# adc08200.net
KiCad netlist of a schematic drawn in Altium Designer
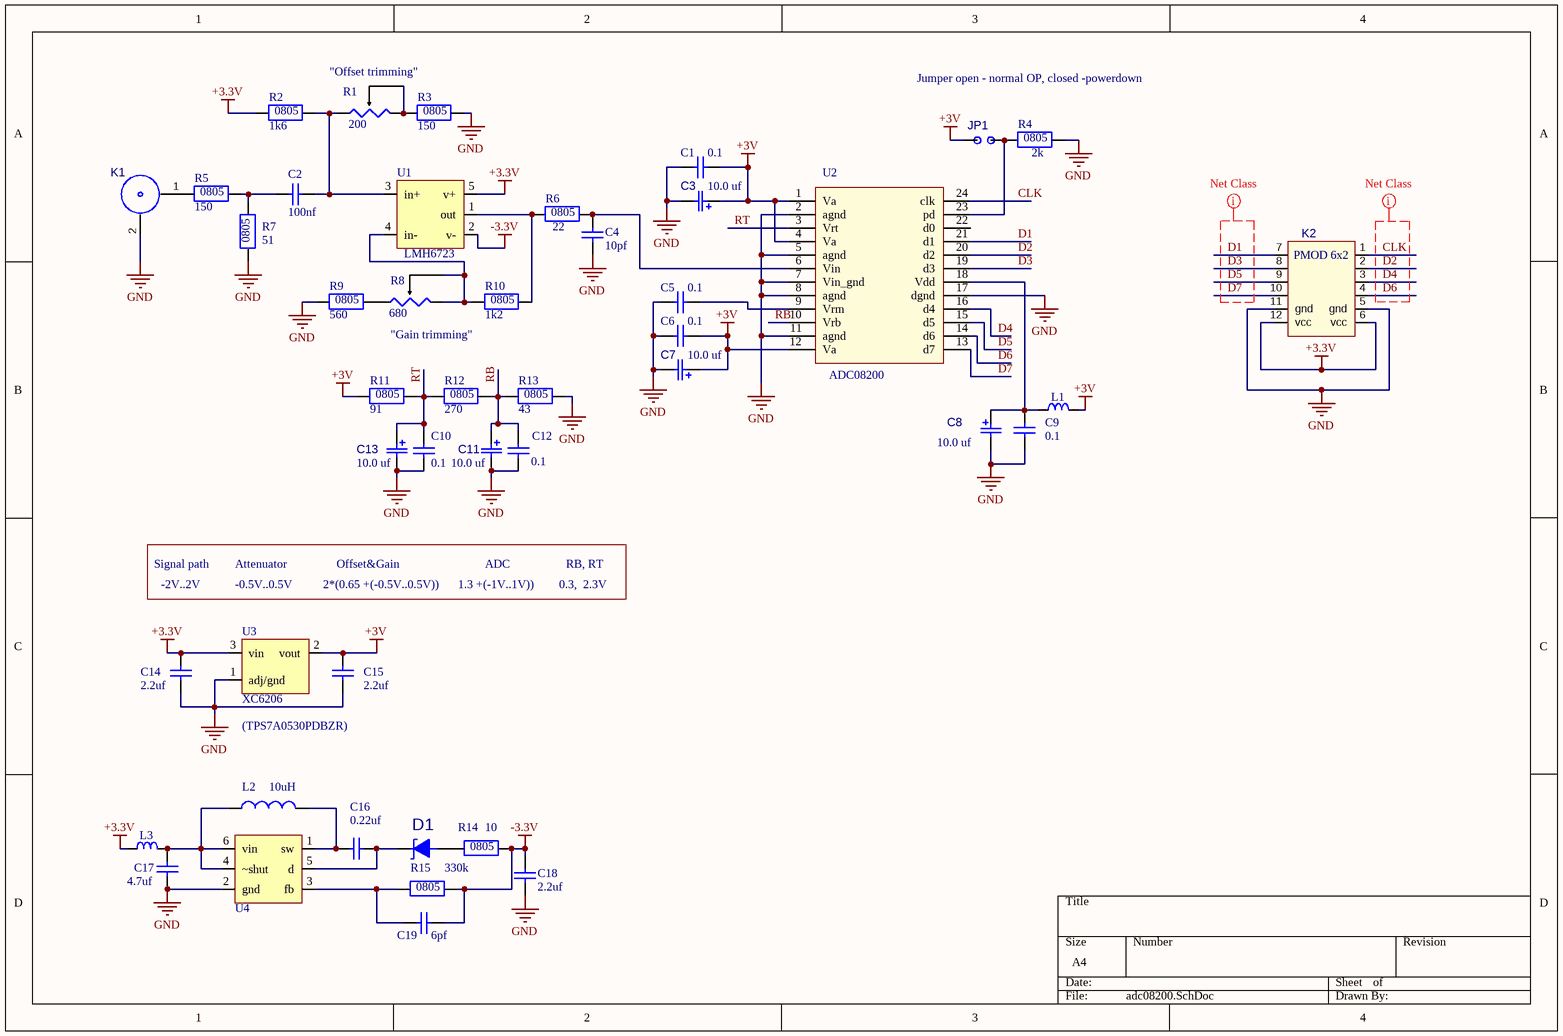
[diagram p0: adc08200.SchDoc]

(export (version "E")
  (design (tool "Eeschema 10.0.6"))
  (components
    (comp (ref "C1")
      (value "0.1")
      (footprint "SM0805")
      (description "Capacitor")
      (fields (field (name "Comment") "cap0805") (field (name "PUBLISHER") "Altium Limited"))
      (libsource (lib "alt2017") (part "cap0805"))
    )
    (comp (ref "C2")
      (value "100nf")
      (footprint "SM0805")
      (description "Capacitor")
      (fields (field (name "Comment") "cap0805") (field (name "PUBLISHER") "Altium Limited"))
      (libsource (lib "alt2017") (part "cap0805"))
    )
    (comp (ref "C3")
      (value "CAP_POL_SMA")
      (footprint "CAP_POL_SMA (3216)")
      (description "CAP_POL_SMA(3216)")
      (fields (field (name "ALTIUM_UNNAMED_1") "10.0 uf"))
      (libsource (lib "alt2017") (part "CAP_POL_SMA"))
    )
    (comp (ref "C4")
      (value "10pf")
      (footprint "SM0805")
      (description "Capacitor")
      (fields (field (name "Comment") "cap0805") (field (name "PUBLISHER") "Altium Limited"))
      (libsource (lib "alt2017") (part "cap0805"))
    )
    (comp (ref "C5")
      (value "0.1")
      (footprint "SM0805")
      (description "Capacitor")
      (fields (field (name "Comment") "cap0805") (field (name "PUBLISHER") "Altium Limited"))
      (libsource (lib "alt2017") (part "cap0805"))
    )
    (comp (ref "C6")
      (value "0.1")
      (footprint "SM0805")
      (description "Capacitor")
      (fields (field (name "Comment") "cap0805") (field (name "PUBLISHER") "Altium Limited"))
      (libsource (lib "alt2017") (part "cap0805"))
    )
    (comp (ref "C7")
      (value "CAP_POL_SMA")
      (footprint "CAP_POL_SMA (3216)")
      (description "CAP_POL_SMA(3216)")
      (fields (field (name "ALTIUM_UNNAMED_1") "10.0 uf"))
      (libsource (lib "alt2017") (part "CAP_POL_SMA"))
    )
    (comp (ref "C8")
      (value "CAP_POL_SMA")
      (footprint "CAP_POL_SMA (3216)")
      (description "CAP_POL_SMA(3216)")
      (fields (field (name "ALTIUM_UNNAMED_1") "10.0 uf"))
      (libsource (lib "alt2017") (part "CAP_POL_SMA"))
    )
    (comp (ref "C9")
      (value "0.1")
      (footprint "SM0805")
      (description "Capacitor")
      (fields (field (name "Comment") "cap0805") (field (name "PUBLISHER") "Altium Limited"))
      (libsource (lib "alt2017") (part "cap0805"))
    )
    (comp (ref "C10")
      (value "0.1")
      (footprint "SM0805")
      (description "Capacitor")
      (fields (field (name "Comment") "cap0805") (field (name "PUBLISHER") "Altium Limited"))
      (libsource (lib "alt2017") (part "cap0805"))
    )
    (comp (ref "C11")
      (value "CAP_POL_SMA")
      (footprint "CAP_POL_SMA (3216)")
      (description "CAP_POL_SMA(3216)")
      (fields (field (name "ALTIUM_UNNAMED_1") "10.0 uf"))
      (libsource (lib "alt2017") (part "CAP_POL_SMA"))
    )
    (comp (ref "C12")
      (value "0.1")
      (footprint "SM0805")
      (description "Capacitor")
      (fields (field (name "Comment") "cap0805") (field (name "PUBLISHER") "Altium Limited"))
      (libsource (lib "alt2017") (part "cap0805"))
    )
    (comp (ref "C13")
      (value "CAP_POL_SMA")
      (footprint "CAP_POL_SMA (3216)")
      (description "CAP_POL_SMA(3216)")
      (fields (field (name "ALTIUM_UNNAMED_1") "10.0 uf"))
      (libsource (lib "alt2017") (part "CAP_POL_SMA"))
    )
    (comp (ref "C14")
      (value "2.2uf")
      (footprint "SM0805")
      (description "Capacitor")
      (fields (field (name "Comment") "cap0805") (field (name "PUBLISHER") "Altium Limited"))
      (libsource (lib "alt2017") (part "cap0805"))
    )
    (comp (ref "C15")
      (value "2.2uf")
      (footprint "SM0805")
      (description "Capacitor")
      (fields (field (name "Comment") "cap0805") (field (name "PUBLISHER") "Altium Limited"))
      (libsource (lib "alt2017") (part "cap0805"))
    )
    (comp (ref "C16")
      (value "0.22uf")
      (footprint "SM0805")
      (description "Capacitor")
      (fields (field (name "Comment") "cap0805") (field (name "PUBLISHER") "Altium Limited"))
      (libsource (lib "alt2017") (part "cap0805"))
    )
    (comp (ref "C17")
      (value "4.7uf")
      (footprint "SM0805")
      (description "Capacitor")
      (fields (field (name "Comment") "cap0805") (field (name "PUBLISHER") "Altium Limited"))
      (libsource (lib "alt2017") (part "cap0805"))
    )
    (comp (ref "C18")
      (value "2.2uf")
      (footprint "SM0805")
      (description "Capacitor")
      (fields (field (name "Comment") "cap0805") (field (name "PUBLISHER") "Altium Limited"))
      (libsource (lib "alt2017") (part "cap0805"))
    )
    (comp (ref "C19")
      (value "6pf")
      (footprint "SM0805")
      (description "Capacitor")
      (fields (field (name "Comment") "cap0805") (field (name "PUBLISHER") "Altium Limited"))
      (libsource (lib "alt2017") (part "cap0805"))
    )
    (comp (ref "D1")
      (value "DiodeShottky_SOD323")
      (footprint "SOD323")
      (description "SOD323")
      (libsource (lib "alt2017") (part "DiodeShottky_SOD323"))
    )
    (comp (ref "JP1") (value "JUMPER2") (footprint "JUMPER2") (libsource (lib "alt2017") (part "JUMPER2")))
    (comp (ref "K1")
      (value "SMA_Edge")
      (footprint "AMPHENOL_132357-11")
      (libsource (lib "alt2017") (part "SMA_Edge"))
    )
    (comp (ref "K2")
      (value "PMOD_6x2_right_angle")
      (footprint "PMOD_6x2_right_ANGLE")
      (libsource (lib "alt2017") (part "PMOD_6x2_right_angle"))
    )
    (comp (ref "L1")
      (value "75R@100MHz")
      (footprint "SM_0805_INDUCTANCE _3D")
      (description "chip inductance")
      (fields
        (field (name "PART NUMBER") "IND0805_MURATA_BLM21BB750SN1D")
        (field (name "POWER") "700mA")
        (field (name "AUTHOR") "S. Jafar")
      )
      (libsource (lib "alt2017") (part "Ind_Chip_0805"))
    )
    (comp (ref "L2")
      (value "inductance SMT 3.2x4.5 mm")
      (footprint "inductor_LQH43PN")
      (fields (field (name "ALTIUM_UNNAMED_1") "10uH"))
      (libsource (lib "alt2017") (part "inductor_LQH43PN"))
    )
    (comp (ref "L3")
      (value "75R@100MHz")
      (footprint "SM_0805_INDUCTANCE _3D")
      (description "chip inductance")
      (fields
        (field (name "PART NUMBER") "IND0805_MURATA_BLM21BB750SN1D")
        (field (name "POWER") "700mA")
        (field (name "AUTHOR") "S. Jafar")
      )
      (libsource (lib "alt2017") (part "Ind_Chip_0805"))
    )
    (comp (ref "R1")
      (value "200")
      (footprint "TRIM_BOURNS_3223W")
      (description "Trimmer  Bourns  3223W")
      (fields (field (name "Comment") "res_var_SMT") (field (name "PUBLISHER") "Altium Limited"))
      (libsource (lib "alt2017") (part "res_var_SMT"))
    )
    (comp (ref "R2")
      (value "1k6")
      (footprint "SM0805")
      (description "Resistor")
      (fields (field (name "Comment") "res0805_EU") (field (name "PUBLISHER") "Altium Limited"))
      (libsource (lib "alt2017") (part "res0805_EU"))
    )
    (comp (ref "R3")
      (value "150")
      (footprint "SM0805")
      (description "Resistor")
      (fields (field (name "Comment") "res0805_EU") (field (name "PUBLISHER") "Altium Limited"))
      (libsource (lib "alt2017") (part "res0805_EU"))
    )
    (comp (ref "R4")
      (value "2k")
      (footprint "SM0805")
      (description "Resistor")
      (fields (field (name "Comment") "res0805_EU") (field (name "PUBLISHER") "Altium Limited"))
      (libsource (lib "alt2017") (part "res0805_EU"))
    )
    (comp (ref "R5")
      (value "150")
      (footprint "SM0805")
      (description "Resistor")
      (fields (field (name "Comment") "res0805_EU") (field (name "PUBLISHER") "Altium Limited"))
      (libsource (lib "alt2017") (part "res0805_EU"))
    )
    (comp (ref "R6")
      (value "22")
      (footprint "SM0805")
      (description "Resistor")
      (fields (field (name "Comment") "res0805_EU") (field (name "PUBLISHER") "Altium Limited"))
      (libsource (lib "alt2017") (part "res0805_EU"))
    )
    (comp (ref "R7")
      (value "51")
      (footprint "SM0805")
      (description "Resistor")
      (fields (field (name "Comment") "res0805_EU") (field (name "PUBLISHER") "Altium Limited"))
      (libsource (lib "") (part "res0805_EU_1"))
    )
    (comp (ref "R8")
      (value "680")
      (footprint "TRIM_BOURNS_3223W")
      (description "Trimmer  Bourns  3223W")
      (fields (field (name "Comment") "res_var_SMT") (field (name "PUBLISHER") "Altium Limited"))
      (libsource (lib "alt2017") (part "res_var_SMT"))
    )
    (comp (ref "R9")
      (value "560")
      (footprint "SM0805")
      (description "Resistor")
      (fields (field (name "Comment") "res0805_EU") (field (name "PUBLISHER") "Altium Limited"))
      (libsource (lib "alt2017") (part "res0805_EU"))
    )
    (comp (ref "R10")
      (value "1k2")
      (footprint "SM0805")
      (description "Resistor")
      (fields (field (name "Comment") "res0805_EU") (field (name "PUBLISHER") "Altium Limited"))
      (libsource (lib "alt2017") (part "res0805_EU"))
    )
    (comp (ref "R11")
      (value "91")
      (footprint "SM0805")
      (description "Resistor")
      (fields (field (name "Comment") "res0805_EU") (field (name "PUBLISHER") "Altium Limited"))
      (libsource (lib "alt2017") (part "res0805_EU"))
    )
    (comp (ref "R12")
      (value "270")
      (footprint "SM0805")
      (description "Resistor")
      (fields (field (name "Comment") "res0805_EU") (field (name "PUBLISHER") "Altium Limited"))
      (libsource (lib "alt2017") (part "res0805_EU"))
    )
    (comp (ref "R13")
      (value "43")
      (footprint "SM0805")
      (description "Resistor")
      (fields (field (name "Comment") "res0805_EU") (field (name "PUBLISHER") "Altium Limited"))
      (libsource (lib "alt2017") (part "res0805_EU"))
    )
    (comp (ref "R14")
      (value "10")
      (footprint "SM0805")
      (description "Resistor")
      (fields (field (name "Comment") "res0805_EU") (field (name "PUBLISHER") "Altium Limited"))
      (libsource (lib "alt2017") (part "res0805_EU"))
    )
    (comp (ref "R15")
      (value "330k")
      (footprint "SM0805")
      (description "Resistor")
      (fields (field (name "Comment") "res0805_EU") (field (name "PUBLISHER") "Altium Limited"))
      (libsource (lib "alt2017") (part "res0805_EU"))
    )
    (comp (ref "U1")
      (value "LMH6723")
      (footprint "SOT-23_5")
      (description "current feedback OPAMP")
      (libsource (lib "alt2017") (part "LMH6723"))
    )
    (comp (ref "U2")
      (value "ADC08200")
      (footprint "SSOP-24")
      (description "soic28 with thermalpad")
      (libsource (lib "alt2017") (part "ADC08200"))
    )
    (comp (ref "U3")
      (value "XC6206")
      (footprint "SOT-23")
      (description "SOT-23-3 ldo")
      (libsource (lib "alt2017") (part "XC6206"))
    )
    (comp (ref "U4")
      (value "LT3483")
      (footprint "SOT-23_6")
      (description "dc/dc tsot23-6")
      (libsource (lib "alt2017") (part "LT3483"))
    )
  )
  (nets
    (net (code "1") (name "+3.3V") (class "Default")
      (node (ref "C14") (pin "2") (pinfunction "2_2") (pintype "passive"))
      (node (ref "K2") (pin "12") (pinfunction "vcc_12") (pintype "passive"))
      (node (ref "K2") (pin "6") (pinfunction "vcc_6") (pintype "passive"))
      (node (ref "L3") (pin "1") (pinfunction "1_1") (pintype "passive"))
      (node (ref "R2") (pin "1") (pinfunction "1_1") (pintype "passive"))
      (node (ref "U1") (pin "5") (pinfunction "v+_5") (pintype "passive"))
      (node (ref "U3") (pin "3") (pinfunction "vin_3") (pintype "passive"))
    )
    (net (code "2") (name "+3V") (class "Default")
      (node (ref "C1") (pin "2") (pinfunction "2_2") (pintype "passive"))
      (node (ref "C15") (pin "2") (pinfunction "2_2") (pintype "passive"))
      (node (ref "C3") (pin "1") (pinfunction "a_1") (pintype "passive"))
      (node (ref "C6") (pin "2") (pinfunction "2_2") (pintype "passive"))
      (node (ref "C7") (pin "1") (pinfunction "a_1") (pintype "passive"))
      (node (ref "JP1") (pin "2") (pinfunction "2_2") (pintype "passive"))
      (node (ref "L1") (pin "2") (pinfunction "2_2") (pintype "passive"))
      (node (ref "R11") (pin "1") (pinfunction "1_1") (pintype "passive"))
      (node (ref "U2") (pin "1") (pinfunction "Va_1") (pintype "passive"))
      (node (ref "U2") (pin "12") (pinfunction "Va_12") (pintype "passive"))
      (node (ref "U2") (pin "4") (pinfunction "Va_4") (pintype "passive"))
      (node (ref "U3") (pin "2") (pinfunction "vout_2") (pintype "passive"))
    )
    (net (code "3") (name "-3.3V") (class "Default")
      (node (ref "C18") (pin "2") (pinfunction "2_2") (pintype "passive"))
      (node (ref "C19") (pin "1") (pinfunction "1_1") (pintype "passive"))
      (node (ref "R14") (pin "2") (pinfunction "2_2") (pintype "passive"))
      (node (ref "R15") (pin "2") (pinfunction "2_2") (pintype "passive"))
      (node (ref "U1") (pin "2") (pinfunction "v-_2") (pintype "passive"))
    )
    (net (code "4") (name "/CLK") (class "Default")
      (node (ref "K2") (pin "1") (pinfunction "1_1") (pintype "passive"))
      (node (ref "U2") (pin "24") (pinfunction "clk_24") (pintype "passive"))
    )
    (net (code "5") (name "/D1") (class "Default")
      (node (ref "K2") (pin "7") (pinfunction "7_7") (pintype "passive"))
      (node (ref "U2") (pin "21") (pinfunction "d1_21") (pintype "passive"))
    )
    (net (code "6") (name "/D2") (class "Default")
      (node (ref "K2") (pin "2") (pinfunction "2_2") (pintype "passive"))
      (node (ref "U2") (pin "20") (pinfunction "d2_20") (pintype "passive"))
    )
    (net (code "7") (name "/D3") (class "Default")
      (node (ref "K2") (pin "8") (pinfunction "8_8") (pintype "passive"))
      (node (ref "U2") (pin "19") (pinfunction "d3_19") (pintype "passive"))
    )
    (net (code "8") (name "/D4") (class "Default")
      (node (ref "K2") (pin "3") (pinfunction "3_3") (pintype "passive"))
      (node (ref "U2") (pin "16") (pinfunction "d4_16") (pintype "passive"))
    )
    (net (code "9") (name "/D5") (class "Default")
      (node (ref "K2") (pin "9") (pinfunction "9_9") (pintype "passive"))
      (node (ref "U2") (pin "15") (pinfunction "d5_15") (pintype "passive"))
    )
    (net (code "10") (name "/D6") (class "Default")
      (node (ref "K2") (pin "4") (pinfunction "4_4") (pintype "passive"))
      (node (ref "U2") (pin "14") (pinfunction "d6_14") (pintype "passive"))
    )
    (net (code "11") (name "/D7") (class "Default")
      (node (ref "K2") (pin "10") (pinfunction "10_10") (pintype "passive"))
      (node (ref "U2") (pin "13") (pinfunction "d7_13") (pintype "passive"))
    )
    (net (code "12") (name "/RB") (class "Default")
      (node (ref "C11") (pin "1") (pinfunction "a_1") (pintype "passive"))
      (node (ref "C12") (pin "2") (pinfunction "2_2") (pintype "passive"))
      (node (ref "R12") (pin "2") (pinfunction "2_2") (pintype "passive"))
      (node (ref "R13") (pin "1") (pinfunction "1_1") (pintype "passive"))
      (node (ref "U2") (pin "10") (pinfunction "Vrb_10") (pintype "passive"))
    )
    (net (code "13") (name "/RT") (class "Default")
      (node (ref "C10") (pin "2") (pinfunction "2_2") (pintype "passive"))
      (node (ref "C13") (pin "1") (pinfunction "a_1") (pintype "passive"))
      (node (ref "R11") (pin "2") (pinfunction "2_2") (pintype "passive"))
      (node (ref "R12") (pin "1") (pinfunction "1_1") (pintype "passive"))
      (node (ref "U2") (pin "3") (pinfunction "Vrt_3") (pintype "passive"))
    )
    (net (code "14") (name "GND") (class "Default")
      (node (ref "C1") (pin "1") (pinfunction "1_1") (pintype "passive"))
      (node (ref "C10") (pin "1") (pinfunction "1_1") (pintype "passive"))
      (node (ref "C11") (pin "2") (pinfunction "b_2") (pintype "passive"))
      (node (ref "C12") (pin "1") (pinfunction "1_1") (pintype "passive"))
      (node (ref "C13") (pin "2") (pinfunction "b_2") (pintype "passive"))
      (node (ref "C14") (pin "1") (pinfunction "1_1") (pintype "passive"))
      (node (ref "C15") (pin "1") (pinfunction "1_1") (pintype "passive"))
      (node (ref "C17") (pin "1") (pinfunction "1_1") (pintype "passive"))
      (node (ref "C18") (pin "1") (pinfunction "1_1") (pintype "passive"))
      (node (ref "C3") (pin "2") (pinfunction "b_2") (pintype "passive"))
      (node (ref "C4") (pin "1") (pinfunction "1_1") (pintype "passive"))
      (node (ref "C5") (pin "1") (pinfunction "1_1") (pintype "passive"))
      (node (ref "C6") (pin "1") (pinfunction "1_1") (pintype "passive"))
      (node (ref "C7") (pin "2") (pinfunction "b_2") (pintype "passive"))
      (node (ref "C8") (pin "2") (pinfunction "b_2") (pintype "passive"))
      (node (ref "C9") (pin "1") (pinfunction "1_1") (pintype "passive"))
      (node (ref "K1") (pin "2") (pinfunction "2_2") (pintype "passive"))
      (node (ref "K2") (pin "11") (pinfunction "gnd_11") (pintype "passive"))
      (node (ref "K2") (pin "5") (pinfunction "gnd_5") (pintype "passive"))
      (node (ref "R13") (pin "2") (pinfunction "2_2") (pintype "passive"))
      (node (ref "R3") (pin "2") (pinfunction "2_2") (pintype "passive"))
      (node (ref "R4") (pin "2") (pinfunction "2_2") (pintype "passive"))
      (node (ref "R7") (pin "1") (pinfunction "1_1") (pintype "passive"))
      (node (ref "R9") (pin "1") (pinfunction "1_1") (pintype "passive"))
      (node (ref "U2") (pin "11") (pinfunction "agnd_11") (pintype "passive"))
      (node (ref "U2") (pin "17") (pinfunction "dgnd_17") (pintype "passive"))
      (node (ref "U2") (pin "2") (pinfunction "agnd_2") (pintype "passive"))
      (node (ref "U2") (pin "5") (pinfunction "agnd_5") (pintype "passive"))
      (node (ref "U2") (pin "7") (pinfunction "Vin_gnd_7") (pintype "passive"))
      (node (ref "U2") (pin "8") (pinfunction "agnd_8") (pintype "passive"))
      (node (ref "U3") (pin "1") (pinfunction "adj/gnd_1") (pintype "passive"))
      (node (ref "U4") (pin "2") (pinfunction "gnd_2") (pintype "passive"))
    )
    (net (code "15") (name "Net-(C2-Pad1)") (class "Default")
      (node (ref "C2") (pin "1") (pinfunction "1_1") (pintype "passive"))
      (node (ref "R5") (pin "2") (pinfunction "2_2") (pintype "passive"))
      (node (ref "R7") (pin "2") (pinfunction "2_2") (pintype "passive"))
    )
    (net (code "16") (name "Net-(C8-a)") (class "Default")
      (node (ref "C8") (pin "1") (pinfunction "a_1") (pintype "passive"))
      (node (ref "C9") (pin "2") (pinfunction "2_2") (pintype "passive"))
      (node (ref "L1") (pin "1") (pinfunction "1_1") (pintype "passive"))
      (node (ref "U2") (pin "18") (pinfunction "Vdd_18") (pintype "passive"))
    )
    (net (code "17") (name "Net-(D1-a)") (class "Default")
      (node (ref "D1") (pin "1") (pinfunction "a_1") (pintype "passive"))
      (node (ref "R14") (pin "1") (pinfunction "1_1") (pintype "passive"))
    )
    (net (code "18") (name "Net-(D1-k)") (class "Default")
      (node (ref "C16") (pin "1") (pinfunction "1_1") (pintype "passive"))
      (node (ref "D1") (pin "2") (pinfunction "k_2") (pintype "passive"))
      (node (ref "U4") (pin "5") (pinfunction "d_5") (pintype "passive"))
    )
    (net (code "19") (name "Net-(K1-Pad1)") (class "Default")
      (node (ref "K1") (pin "1") (pinfunction "1_1") (pintype "passive"))
      (node (ref "R5") (pin "1") (pinfunction "1_1") (pintype "passive"))
    )
    (net (code "20") (name "Net-(R1-Pad2)") (class "Default")
      (node (ref "R1") (pin "2") (pinfunction "2_2") (pintype "passive"))
      (node (ref "R1") (pin "3") (pinfunction "3_3") (pintype "passive"))
      (node (ref "R3") (pin "1") (pinfunction "1_1") (pintype "passive"))
    )
    (net (code "21") (name "Net-(R8-Pad1)") (class "Default")
      (node (ref "R8") (pin "1") (pinfunction "1_1") (pintype "passive"))
      (node (ref "R9") (pin "2") (pinfunction "2_2") (pintype "passive"))
    )
    (net (code "22") (name "Net-(U1-in+)") (class "Default")
      (node (ref "C2") (pin "2") (pinfunction "2_2") (pintype "passive"))
      (node (ref "R1") (pin "1") (pinfunction "1_1") (pintype "passive"))
      (node (ref "R2") (pin "2") (pinfunction "2_2") (pintype "passive"))
      (node (ref "U1") (pin "3") (pinfunction "in+_3") (pintype "passive"))
    )
    (net (code "23") (name "Net-(U1-in-)") (class "Default")
      (node (ref "R10") (pin "1") (pinfunction "1_1") (pintype "passive"))
      (node (ref "R8") (pin "2") (pinfunction "2_2") (pintype "passive"))
      (node (ref "R8") (pin "3") (pinfunction "3_3") (pintype "passive"))
      (node (ref "U1") (pin "4") (pinfunction "in-_4") (pintype "passive"))
    )
    (net (code "24") (name "Net-(U1-out)") (class "Default")
      (node (ref "R10") (pin "2") (pinfunction "2_2") (pintype "passive"))
      (node (ref "R6") (pin "1") (pinfunction "1_1") (pintype "passive"))
      (node (ref "U1") (pin "1") (pinfunction "out_1") (pintype "passive"))
    )
    (net (code "25") (name "Net-(U2-Vin)") (class "Default")
      (node (ref "C4") (pin "2") (pinfunction "2_2") (pintype "passive"))
      (node (ref "R6") (pin "2") (pinfunction "2_2") (pintype "passive"))
      (node (ref "U2") (pin "6") (pinfunction "Vin_6") (pintype "passive"))
    )
    (net (code "26") (name "Net-(U2-Vrm)") (class "Default")
      (node (ref "C5") (pin "2") (pinfunction "2_2") (pintype "passive"))
      (node (ref "U2") (pin "9") (pinfunction "Vrm_9") (pintype "passive"))
    )
    (net (code "27") (name "Net-(U2-pd)") (class "Default")
      (node (ref "JP1") (pin "1") (pinfunction "1_1") (pintype "passive"))
      (node (ref "R4") (pin "1") (pinfunction "1_1") (pintype "passive"))
      (node (ref "U2") (pin "23") (pinfunction "pd_23") (pintype "passive"))
    )
    (net (code "28") (name "Net-(U4-fb)") (class "Default")
      (node (ref "C19") (pin "2") (pinfunction "2_2") (pintype "passive"))
      (node (ref "R15") (pin "1") (pinfunction "1_1") (pintype "passive"))
      (node (ref "U4") (pin "3") (pinfunction "fb_3") (pintype "passive"))
    )
    (net (code "29") (name "Net-(U4-sw)") (class "Default")
      (node (ref "C16") (pin "2") (pinfunction "2_2") (pintype "passive"))
      (node (ref "L2") (pin "2") (pinfunction "2_2") (pintype "passive"))
      (node (ref "U4") (pin "1") (pinfunction "sw_1") (pintype "passive"))
    )
    (net (code "30") (name "Net-(U4-vin)") (class "Default")
      (node (ref "C17") (pin "2") (pinfunction "2_2") (pintype "passive"))
      (node (ref "L2") (pin "1") (pinfunction "1_1") (pintype "passive"))
      (node (ref "L3") (pin "2") (pinfunction "2_2") (pintype "passive"))
      (node (ref "U4") (pin "4") (pinfunction "~shut_4") (pintype "passive"))
      (node (ref "U4") (pin "6") (pinfunction "vin_6") (pintype "passive"))
    )
    (net (code "31") (name "unconnected-(U2-d0-Pad22)") (class "Default")
      (node (ref "U2") (pin "22") (pinfunction "d0_22") (pintype "passive"))
    )
  )
)
